# PIC32MK.net
KiCad netlist of a schematic drawn in Altium Designer
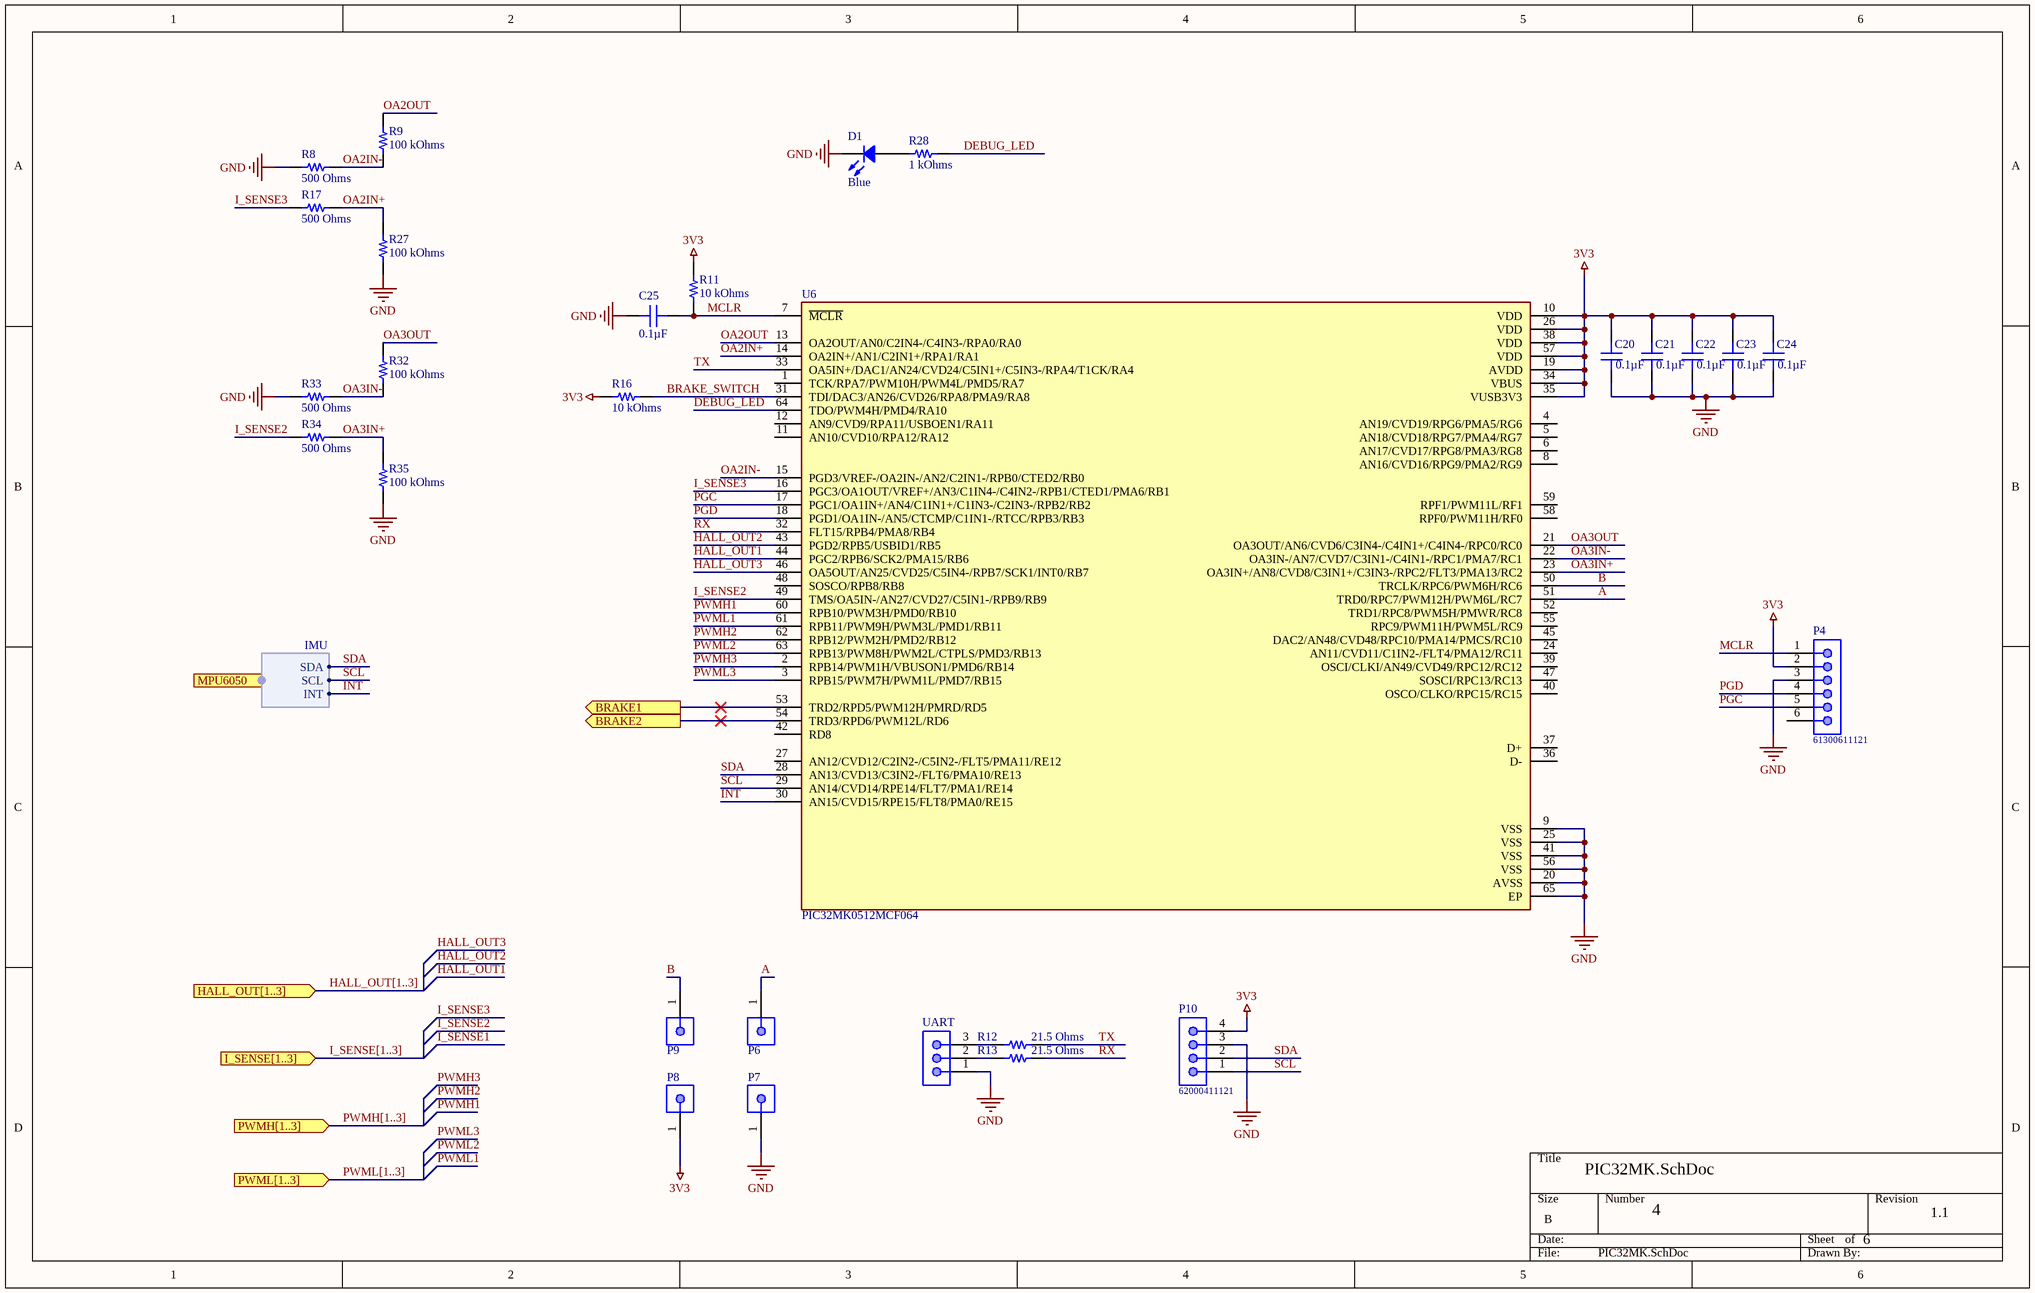
[diagram p0: PIC32MK.SchDoc]

(export (version "E")
  (design (tool "Eeschema 10.0.6"))
  (components
    (comp (ref "C20")
      (value "0.1µF")
      (footprint "CAP 0603_1608")
      (description "CAP CER 0.1UF 100V 0603 EPOXY")
      (fields
        (field (name "PART NUMBER") "GCG188R92A104KA03D")
        (field (name "MANUFACTURER") "Murata Electronics")
      )
      (libsource (lib "Celestial Altium Library - altium_library") (part "Capacitor"))
    )
    (comp (ref "C21")
      (value "0.1µF")
      (footprint "CAP 0603_1608")
      (description "CAP CER 0.1UF 100V 0603 EPOXY")
      (fields
        (field (name "PART NUMBER") "GCG188R92A104KA03D")
        (field (name "MANUFACTURER") "Murata Electronics")
      )
      (libsource (lib "Celestial Altium Library - altium_library") (part "Capacitor"))
    )
    (comp (ref "C22")
      (value "0.1µF")
      (footprint "CAP 0603_1608")
      (description "CAP CER 0.1UF 100V 0603 EPOXY")
      (fields
        (field (name "PART NUMBER") "GCG188R92A104KA03D")
        (field (name "MANUFACTURER") "Murata Electronics")
      )
      (libsource (lib "Celestial Altium Library - altium_library") (part "Capacitor"))
    )
    (comp (ref "C23")
      (value "0.1µF")
      (footprint "CAP 0603_1608")
      (description "CAP CER 0.1UF 100V 0603 EPOXY")
      (fields
        (field (name "PART NUMBER") "GCG188R92A104KA03D")
        (field (name "MANUFACTURER") "Murata Electronics")
      )
      (libsource (lib "Celestial Altium Library - altium_library") (part "Capacitor"))
    )
    (comp (ref "C24")
      (value "0.1µF")
      (footprint "CAP 0603_1608")
      (description "CAP CER 0.1UF 100V 0603 EPOXY")
      (fields
        (field (name "PART NUMBER") "GCG188R92A104KA03D")
        (field (name "MANUFACTURER") "Murata Electronics")
      )
      (libsource (lib "Celestial Altium Library - altium_library") (part "Capacitor"))
    )
    (comp (ref "C25")
      (value "0.1µF")
      (footprint "CAP 0603_1608")
      (description "CAP CER 0.1UF 100V 0603 EPOXY")
      (fields
        (field (name "PART NUMBER") "GCG188R92A104KA03D")
        (field (name "MANUFACTURER") "Murata Electronics")
      )
      (libsource (lib "Celestial Altium Library - altium_library") (part "Capacitor"))
    )
    (comp (ref "D1")
      (value "Blue")
      (footprint "LED 0603_1608 GREEN")
      (description "Blue LED")
      (fields (field (name "PART NUMBER") "XZCDGK53W-8VF") (field (name "MANUFACTURER") "SunLED"))
      (libsource (lib "Celestial Altium Library - altium_library") (part "LED"))
    )
    (comp (ref "P4")
      (value "61300611121")
      (footprint "61300611121")
      (description "WR-PHD Pin Header, THT, pitch 2.54mm, Single Row, Vertical, 6p")
      (fields (field (name "MANUFACTURER") "Wurth Elektronik"))
      (libsource (lib "Altium_WR-PHD") (part "61300611121"))
    )
    (comp (ref "P6")
      (value "61300111121")
      (footprint "61300111121")
      (description "WR-PHD Pin Header, THT, pitch 2.54mm, Single Row, Vertical, 1p")
      (fields (field (name "MANUFACTURER") "Wurth Elektronik"))
      (libsource (lib "Altium_WR-PHD") (part "61300111121"))
    )
    (comp (ref "P7")
      (value "61300111121")
      (footprint "61300111121")
      (description "WR-PHD Pin Header, THT, pitch 2.54mm, Single Row, Vertical, 1p")
      (fields (field (name "MANUFACTURER") "Wurth Elektronik"))
      (libsource (lib "Altium_WR-PHD") (part "61300111121"))
    )
    (comp (ref "P8")
      (value "61300111121")
      (footprint "61300111121")
      (description "WR-PHD Pin Header, THT, pitch 2.54mm, Single Row, Vertical, 1p")
      (fields (field (name "MANUFACTURER") "Wurth Elektronik"))
      (libsource (lib "Altium_WR-PHD") (part "61300111121"))
    )
    (comp (ref "P9")
      (value "61300111121")
      (footprint "61300111121")
      (description "WR-PHD Pin Header, THT, pitch 2.54mm, Single Row, Vertical, 1p")
      (fields (field (name "MANUFACTURER") "Wurth Elektronik"))
      (libsource (lib "Altium_WR-PHD") (part "61300111121"))
    )
    (comp (ref "P10")
      (value "62000411121")
      (footprint "62000411121")
      (description "WR-PHD Pin Header, THT, pitch 2mm, Single Row, Vertical, 4p")
      (fields (field (name "MANUFACTURER") "Wurth Elektronik"))
      (libsource (lib "Altium_WR-PHD") (part "62000411121"))
    )
    (comp (ref "R8")
      (value "500 Ohms")
      (footprint "RES 0603_1608")
      (description "RES SMD 500 OHM 0.05% 1/10W 0603")
      (fields (field (name "PART NUMBER") "TNPU0603500RAZEN00") (field (name "MANUFACTURER") "Vishay Dale"))
      (libsource (lib "Celestial Altium Library - altium_library") (part "Resistor"))
    )
    (comp (ref "R9")
      (value "100 kOhms")
      (footprint "RES 0603_1608")
      (description "RES SMD 100K OHM 1% 1/4W 0603")
      (fields (field (name "PART NUMBER") "RCA0603100KFKEAHP") (field (name "MANUFACTURER") "Vishay Dale"))
      (libsource (lib "Celestial Altium Library - altium_library") (part "Resistor"))
    )
    (comp (ref "R11")
      (value "10 kOhms")
      (footprint "RES 0603_1608")
      (description "RES 10K OHM 0.1% 1/16W 0603")
      (fields
        (field (name "PART NUMBER") "RNCS0603BKE10K0")
        (field (name "MANUFACTURER") "Stackpole Electronics Inc")
      )
      (libsource (lib "Celestial Altium Library - altium_library") (part "Resistor"))
    )
    (comp (ref "R12")
      (value "21.5 Ohms")
      (footprint "RES 0603_1608")
      (description "RES SMD 21.5 OHM 1% 1/10W 0603")
      (fields
        (field (name "PART NUMBER") "ERJ-3EKF21R5V")
        (field (name "MANUFACTURER") "Panasonic Electronic Components")
      )
      (libsource (lib "Celestial Altium Library - altium_library") (part "Resistor"))
    )
    (comp (ref "R13")
      (value "21.5 Ohms")
      (footprint "RES 0603_1608")
      (description "RES SMD 21.5 OHM 1% 1/10W 0603")
      (fields
        (field (name "PART NUMBER") "ERJ-3EKF21R5V")
        (field (name "MANUFACTURER") "Panasonic Electronic Components")
      )
      (libsource (lib "Celestial Altium Library - altium_library") (part "Resistor"))
    )
    (comp (ref "R16")
      (value "10 kOhms")
      (footprint "RES 0603_1608")
      (description "RES 10K OHM 0.1% 1/16W 0603")
      (fields
        (field (name "PART NUMBER") "RNCS0603BKE10K0")
        (field (name "MANUFACTURER") "Stackpole Electronics Inc")
      )
      (libsource (lib "Celestial Altium Library - altium_library") (part "Resistor"))
    )
    (comp (ref "R17")
      (value "500 Ohms")
      (footprint "RES 0603_1608")
      (description "RES SMD 500 OHM 0.05% 1/10W 0603")
      (fields (field (name "PART NUMBER") "TNPU0603500RAZEN00") (field (name "MANUFACTURER") "Vishay Dale"))
      (libsource (lib "Celestial Altium Library - altium_library") (part "Resistor"))
    )
    (comp (ref "R27")
      (value "100 kOhms")
      (footprint "RES 0603_1608")
      (description "RES SMD 100K OHM 1% 1/4W 0603")
      (fields (field (name "PART NUMBER") "RCA0603100KFKEAHP") (field (name "MANUFACTURER") "Vishay Dale"))
      (libsource (lib "Celestial Altium Library - altium_library") (part "Resistor"))
    )
    (comp (ref "R28")
      (value "1 kOhms")
      (footprint "RES 0603_1608")
      (description "RES 1K OHM 0.5% 1/10W 0603")
      (fields
        (field (name "PART NUMBER") "RNCF0603DTE1K00")
        (field (name "MANUFACTURER") "Stackpole Electronics Inc")
      )
      (libsource (lib "Celestial Altium Library - altium_library") (part "Resistor"))
    )
    (comp (ref "R32")
      (value "100 kOhms")
      (footprint "RES 0603_1608")
      (description "RES SMD 100K OHM 1% 1/4W 0603")
      (fields (field (name "PART NUMBER") "RCA0603100KFKEAHP") (field (name "MANUFACTURER") "Vishay Dale"))
      (libsource (lib "Celestial Altium Library - altium_library") (part "Resistor"))
    )
    (comp (ref "R33")
      (value "500 Ohms")
      (footprint "RES 0603_1608")
      (description "RES SMD 500 OHM 0.05% 1/10W 0603")
      (fields (field (name "PART NUMBER") "TNPU0603500RAZEN00") (field (name "MANUFACTURER") "Vishay Dale"))
      (libsource (lib "Celestial Altium Library - altium_library") (part "Resistor"))
    )
    (comp (ref "R34")
      (value "500 Ohms")
      (footprint "RES 0603_1608")
      (description "RES SMD 500 OHM 0.05% 1/10W 0603")
      (fields (field (name "PART NUMBER") "TNPU0603500RAZEN00") (field (name "MANUFACTURER") "Vishay Dale"))
      (libsource (lib "Celestial Altium Library - altium_library") (part "Resistor"))
    )
    (comp (ref "R35")
      (value "100 kOhms")
      (footprint "RES 0603_1608")
      (description "RES SMD 100K OHM 1% 1/4W 0603")
      (fields (field (name "PART NUMBER") "RCA0603100KFKEAHP") (field (name "MANUFACTURER") "Vishay Dale"))
      (libsource (lib "Celestial Altium Library - altium_library") (part "Resistor"))
    )
    (comp (ref "U6")
      (value "PIC32MK0512MCF064")
      (footprint "QFN50P900X900X100-65N")
      (description "PIC32MK Microcontroller IC 32-Bit 120MHz 1MB _1M x 8_ FLASH 64-TQFP _10x10_")
      (fields
        (field (name "MP") "PIC32MK1024MCF064-I/PT")
        (field (name "DIGI-KEY_PART_NUMBER") "PIC32MK1024MCF064-I/PT-ND")
      )
      (libsource (lib "IC") (part "PIC32MK0512MCF064"))
    )
    (comp (ref "UART")
      (value "3 pin 2mm JST Male")
      (footprint "3pin - 2mm header")
      (libsource (lib "IC") (part "3 pin 2mm JST Male"))
    )
  )
  (nets
    (net (code "2") (name "/A") (class "Default")
      (node (ref "P6") (pin "1") (pinfunction "1_1") (pintype "passive"))
      (node (ref "U6") (pin "51") (pinfunction "TRD0/RPC7/PWM12H/PWM6L/RC7_51") (pintype "passive"))
    )
    (net (code "3") (name "/B") (class "Default")
      (node (ref "P9") (pin "1") (pinfunction "1_1") (pintype "passive"))
      (node (ref "U6") (pin "50") (pinfunction "TRCLK/RPC6/PWM6H/RC6_50") (pintype "passive"))
    )
    (net (code "4") (name "/BRAKE1") (class "Default")
      (node (ref "U6") (pin "53") (pinfunction "TRD2/RPD5/PWM12H/PMRD/RD5_53") (pintype "passive"))
    )
    (net (code "5") (name "/BRAKE2") (class "Default")
      (node (ref "U6") (pin "54") (pinfunction "TRD3/RPD6/PWM12L/RD6_54") (pintype "passive"))
    )
    (net (code "6") (name "/BRAKE_SWITCH") (class "Default")
      (node (ref "R16") (pin "1") (pinfunction "1_1") (pintype "passive"))
      (node (ref "U6") (pin "31") (pinfunction "TDI/DAC3/AN26/CVD26/RPA8/PMA9/RA8_31") (pintype "passive"))
    )
    (net (code "7") (name "/DEBUG_LED") (class "Default")
      (node (ref "R28") (pin "1") (pinfunction "1_1") (pintype "passive"))
      (node (ref "U6") (pin "64") (pinfunction "TDO/PWM4H/PMD4/RA10_64") (pintype "passive"))
    )
    (net (code "8") (name "/HALL_OUT1") (class "Default")
      (node (ref "U6") (pin "44") (pinfunction "PGC2/RPB6/SCK2/PMA15/RB6_44") (pintype "passive"))
    )
    (net (code "9") (name "/HALL_OUT2") (class "Default")
      (node (ref "U6") (pin "43") (pinfunction "PGD2/RPB5/USBID1/RB5_43") (pintype "passive"))
    )
    (net (code "10") (name "/HALL_OUT3") (class "Default")
      (node (ref "U6") (pin "46") (pinfunction "OA5OUT/AN25/CVD25/C5IN4-/RPB7/SCK1/INT0/RB7_46") (pintype "passive"))
    )
    (net (code "12") (name "/INT") (class "Default")
      (node (ref "U6") (pin "30") (pinfunction "AN15/CVD15/RPE15/FLT8/PMA0/RE15_30") (pintype "passive"))
    )
    (net (code "14") (name "/I_SENSE2") (class "Default")
      (node (ref "R34") (pin "1") (pinfunction "1_1") (pintype "passive"))
      (node (ref "U6") (pin "49") (pinfunction "TMS/OA5IN-/AN27/CVD27/C5IN1-/RPB9/RB9_49") (pintype "passive"))
    )
    (net (code "15") (name "/I_SENSE3") (class "Default")
      (node (ref "R17") (pin "1") (pinfunction "1_1") (pintype "passive"))
      (node (ref "U6") (pin "16") (pinfunction "PGC3/OA1OUT/VREF+/AN3/C1IN4-/C4IN2-/RPB1/CTED1/PMA6/RB1_16") (pintype "passive"))
    )
    (net (code "17") (name "/MCLR") (class "Default")
      (node (ref "C25") (pin "1") (pinfunction "1_1") (pintype "passive"))
      (node (ref "P4") (pin "1") (pinfunction "1_1") (pintype "passive"))
      (node (ref "R11") (pin "1") (pinfunction "1_1") (pintype "passive"))
      (node (ref "U6") (pin "7") (pinfunction "~{MCLR}_7") (pintype "passive"))
    )
    (net (code "18") (name "/OA2IN+") (class "Default")
      (node (ref "R17") (pin "2") (pinfunction "2_2") (pintype "passive"))
      (node (ref "R27") (pin "2") (pinfunction "2_2") (pintype "passive"))
      (node (ref "U6") (pin "14") (pinfunction "OA2IN+/AN1/C2IN1+/RPA1/RA1_14") (pintype "passive"))
    )
    (net (code "19") (name "/OA2IN-") (class "Default")
      (node (ref "R8") (pin "2") (pinfunction "2_2") (pintype "passive"))
      (node (ref "R9") (pin "1") (pinfunction "1_1") (pintype "passive"))
      (node (ref "U6") (pin "15") (pinfunction "PGD3/VREF-/OA2IN-/AN2/C2IN1-/RPB0/CTED2/RB0_15") (pintype "passive"))
    )
    (net (code "20") (name "/OA2OUT") (class "Default")
      (node (ref "R9") (pin "2") (pinfunction "2_2") (pintype "passive"))
      (node (ref "U6") (pin "13") (pinfunction "OA2OUT/AN0/C2IN4-/C4IN3-/RPA0/RA0_13") (pintype "passive"))
    )
    (net (code "21") (name "/OA3IN+") (class "Default")
      (node (ref "R34") (pin "2") (pinfunction "2_2") (pintype "passive"))
      (node (ref "R35") (pin "2") (pinfunction "2_2") (pintype "passive"))
      (node (ref "U6") (pin "23") (pinfunction "OA3IN+/AN8/CVD8/C3IN1+/C3IN3-/RPC2/FLT3/PMA13/RC2_23") (pintype "passive"))
    )
    (net (code "22") (name "/OA3IN-") (class "Default")
      (node (ref "R32") (pin "1") (pinfunction "1_1") (pintype "passive"))
      (node (ref "R33") (pin "2") (pinfunction "2_2") (pintype "passive"))
      (node (ref "U6") (pin "22") (pinfunction "OA3IN-/AN7/CVD7/C3IN1-/C4IN1-/RPC1/PMA7/RC1_22") (pintype "passive"))
    )
    (net (code "23") (name "/OA3OUT") (class "Default")
      (node (ref "R32") (pin "2") (pinfunction "2_2") (pintype "passive"))
      (node (ref "U6") (pin "21") (pinfunction "OA3OUT/AN6/CVD6/C3IN4-/C4IN1+/C4IN4-/RPC0/RC0_21") (pintype "passive"))
    )
    (net (code "24") (name "/PGC") (class "Default")
      (node (ref "P4") (pin "5") (pinfunction "5_5") (pintype "passive"))
      (node (ref "U6") (pin "17") (pinfunction "PGC1/OA1IN+/AN4/C1IN1+/C1IN3-/C2IN3-/RPB2/RB2_17") (pintype "passive"))
    )
    (net (code "25") (name "/PGD") (class "Default")
      (node (ref "P4") (pin "4") (pinfunction "4_4") (pintype "passive"))
      (node (ref "U6") (pin "18") (pinfunction "PGD1/OA1IN-/AN5/CTCMP/C1IN1-/RTCC/RPB3/RB3_18") (pintype "passive"))
    )
    (net (code "26") (name "/PWMH1") (class "Default")
      (node (ref "U6") (pin "60") (pinfunction "RPB10/PWM3H/PMD0/RB10_60") (pintype "passive"))
    )
    (net (code "27") (name "/PWMH2") (class "Default")
      (node (ref "U6") (pin "62") (pinfunction "RPB12/PWM2H/PMD2/RB12_62") (pintype "passive"))
    )
    (net (code "28") (name "/PWMH3") (class "Default")
      (node (ref "U6") (pin "2") (pinfunction "RPB14/PWM1H/VBUSON1/PMD6/RB14_2") (pintype "passive"))
    )
    (net (code "30") (name "/PWML1") (class "Default")
      (node (ref "U6") (pin "61") (pinfunction "RPB11/PWM9H/PWM3L/PMD1/RB11_61") (pintype "passive"))
    )
    (net (code "31") (name "/PWML2") (class "Default")
      (node (ref "U6") (pin "63") (pinfunction "RPB13/PWM8H/PWM2L/CTPLS/PMD3/RB13_63") (pintype "passive"))
    )
    (net (code "32") (name "/PWML3") (class "Default")
      (node (ref "U6") (pin "3") (pinfunction "RPB15/PWM7H/PWM1L/PMD7/RB15_3") (pintype "passive"))
    )
    (net (code "34") (name "/RX") (class "Default")
      (node (ref "R13") (pin "2") (pinfunction "2_2") (pintype "passive"))
      (node (ref "U6") (pin "32") (pinfunction "FLT15/RPB4/PMA8/RB4_32") (pintype "passive"))
    )
    (net (code "35") (name "/SCL") (class "Default")
      (node (ref "P10") (pin "1") (pinfunction "1_1") (pintype "passive"))
      (node (ref "U6") (pin "29") (pinfunction "AN14/CVD14/RPE14/FLT7/PMA1/RE14_29") (pintype "passive"))
    )
    (net (code "36") (name "/SDA") (class "Default")
      (node (ref "P10") (pin "2") (pinfunction "2_2") (pintype "passive"))
      (node (ref "U6") (pin "28") (pinfunction "AN13/CVD13/C3IN2-/FLT6/PMA10/RE13_28") (pintype "passive"))
    )
    (net (code "37") (name "/TX") (class "Default")
      (node (ref "R12") (pin "2") (pinfunction "2_2") (pintype "passive"))
      (node (ref "U6") (pin "33") (pinfunction "OA5IN+/DAC1/AN24/CVD24/C5IN1+/C5IN3-/RPA4/T1CK/RA4_33") (pintype "passive"))
    )
    (net (code "39") (name "3V3") (class "Default")
      (node (ref "C20") (pin "1") (pinfunction "1_1") (pintype "passive"))
      (node (ref "C21") (pin "1") (pinfunction "1_1") (pintype "passive"))
      (node (ref "C22") (pin "1") (pinfunction "1_1") (pintype "passive"))
      (node (ref "C23") (pin "1") (pinfunction "1_1") (pintype "passive"))
      (node (ref "C24") (pin "1") (pinfunction "1_1") (pintype "passive"))
      (node (ref "P10") (pin "4") (pinfunction "4_4") (pintype "passive"))
      (node (ref "P4") (pin "2") (pinfunction "2_2") (pintype "passive"))
      (node (ref "P8") (pin "1") (pinfunction "1_1") (pintype "passive"))
      (node (ref "R11") (pin "2") (pinfunction "2_2") (pintype "passive"))
      (node (ref "R16") (pin "2") (pinfunction "2_2") (pintype "passive"))
      (node (ref "U6") (pin "10") (pinfunction "VDD_10") (pintype "power_in"))
      (node (ref "U6") (pin "19") (pinfunction "AVDD_19") (pintype "power_in"))
      (node (ref "U6") (pin "26") (pinfunction "VDD_26") (pintype "power_in"))
      (node (ref "U6") (pin "34") (pinfunction "VBUS_34") (pintype "power_in"))
      (node (ref "U6") (pin "35") (pinfunction "VUSB3V3_35") (pintype "passive"))
      (node (ref "U6") (pin "38") (pinfunction "VDD_38") (pintype "power_in"))
      (node (ref "U6") (pin "57") (pinfunction "VDD_57") (pintype "power_in"))
    )
    (net (code "40") (name "GND") (class "Default")
      (node (ref "C20") (pin "2") (pinfunction "2_2") (pintype "passive"))
      (node (ref "C21") (pin "2") (pinfunction "2_2") (pintype "passive"))
      (node (ref "C22") (pin "2") (pinfunction "2_2") (pintype "passive"))
      (node (ref "C23") (pin "2") (pinfunction "2_2") (pintype "passive"))
      (node (ref "C24") (pin "2") (pinfunction "2_2") (pintype "passive"))
      (node (ref "C25") (pin "2") (pinfunction "2_2") (pintype "passive"))
      (node (ref "D1") (pin "2") (pinfunction "2_2") (pintype "passive"))
      (node (ref "P10") (pin "3") (pinfunction "3_3") (pintype "passive"))
      (node (ref "P4") (pin "3") (pinfunction "3_3") (pintype "passive"))
      (node (ref "P7") (pin "1") (pinfunction "1_1") (pintype "passive"))
      (node (ref "R27") (pin "1") (pinfunction "1_1") (pintype "passive"))
      (node (ref "R33") (pin "1") (pinfunction "1_1") (pintype "passive"))
      (node (ref "R35") (pin "1") (pinfunction "1_1") (pintype "passive"))
      (node (ref "R8") (pin "1") (pinfunction "1_1") (pintype "passive"))
      (node (ref "U6") (pin "20") (pinfunction "AVSS_20") (pintype "power_in"))
      (node (ref "U6") (pin "25") (pinfunction "VSS_25") (pintype "power_in"))
      (node (ref "U6") (pin "41") (pinfunction "VSS_41") (pintype "power_in"))
      (node (ref "U6") (pin "56") (pinfunction "VSS_56") (pintype "power_in"))
      (node (ref "U6") (pin "65") (pinfunction "EP_65") (pintype "power_in"))
      (node (ref "U6") (pin "9") (pinfunction "VSS_9") (pintype "power_in"))
      (node (ref "UART") (pin "1") (pinfunction "1_1") (pintype "passive"))
    )
    (net (code "41") (name "Net-(D1-Pad1)") (class "Default")
      (node (ref "D1") (pin "1") (pinfunction "1_1") (pintype "passive"))
      (node (ref "R28") (pin "2") (pinfunction "2_2") (pintype "passive"))
    )
    (net (code "42") (name "Net-(R12-Pad1)") (class "Default")
      (node (ref "R12") (pin "1") (pinfunction "1_1") (pintype "passive"))
      (node (ref "UART") (pin "3") (pinfunction "3_3") (pintype "passive"))
    )
    (net (code "43") (name "Net-(R13-Pad1)") (class "Default")
      (node (ref "R13") (pin "1") (pinfunction "1_1") (pintype "passive"))
      (node (ref "UART") (pin "2") (pinfunction "2_2") (pintype "passive"))
    )
    (net (code "44") (name "unconnected-(P4-Pad6)") (class "Default")
      (node (ref "P4") (pin "6") (pinfunction "6_6") (pintype "passive"))
    )
    (net (code "45") (name "unconnected-(U6-AN9{slash}CVD9{slash}RPA11{slash}USBOEN1{slash}RA11-Pad12)") (class "Default")
      (node (ref "U6") (pin "12") (pinfunction "AN9/CVD9/RPA11/USBOEN1/RA11_12") (pintype "passive"))
    )
    (net (code "46") (name "unconnected-(U6-AN10{slash}CVD10{slash}RPA12{slash}RA12-Pad11)") (class "Default")
      (node (ref "U6") (pin "11") (pinfunction "AN10/CVD10/RPA12/RA12_11") (pintype "passive"))
    )
    (net (code "47") (name "unconnected-(U6-AN11{slash}CVD11{slash}C1IN2-{slash}FLT4{slash}PMA12{slash}RC11-Pad24)") (class "Default")
      (node (ref "U6") (pin "24") (pinfunction "AN11/CVD11/C1IN2-/FLT4/PMA12/RC11_24") (pintype "passive"))
    )
    (net (code "48") (name "unconnected-(U6-AN12{slash}CVD12{slash}C2IN2-{slash}C5IN2-{slash}FLT5{slash}PMA11{slash}RE12-Pad27)") (class "Default")
      (node (ref "U6") (pin "27") (pinfunction "AN12/CVD12/C2IN2-/C5IN2-/FLT5/PMA11/RE12_27") (pintype "passive"))
    )
    (net (code "49") (name "unconnected-(U6-AN16{slash}CVD16{slash}RPG9{slash}PMA2{slash}RG9-Pad8)") (class "Default")
      (node (ref "U6") (pin "8") (pinfunction "AN16/CVD16/RPG9/PMA2/RG9_8") (pintype "passive"))
    )
    (net (code "50") (name "unconnected-(U6-AN17{slash}CVD17{slash}RPG8{slash}PMA3{slash}RG8-Pad6)") (class "Default")
      (node (ref "U6") (pin "6") (pinfunction "AN17/CVD17/RPG8/PMA3/RG8_6") (pintype "passive"))
    )
    (net (code "51") (name "unconnected-(U6-AN18{slash}CVD18{slash}RPG7{slash}PMA4{slash}RG7-Pad5)") (class "Default")
      (node (ref "U6") (pin "5") (pinfunction "AN18/CVD18/RPG7/PMA4/RG7_5") (pintype "passive"))
    )
    (net (code "52") (name "unconnected-(U6-AN19{slash}CVD19{slash}RPG6{slash}PMA5{slash}RG6-Pad4)") (class "Default")
      (node (ref "U6") (pin "4") (pinfunction "AN19/CVD19/RPG6/PMA5/RG6_4") (pintype "passive"))
    )
    (net (code "53") (name "unconnected-(U6-D+-Pad37)") (class "Default")
      (node (ref "U6") (pin "37") (pinfunction "D+_37") (pintype "passive"))
    )
    (net (code "54") (name "unconnected-(U6-D--Pad36)") (class "Default")
      (node (ref "U6") (pin "36") (pinfunction "D-_36") (pintype "passive"))
    )
    (net (code "55") (name "unconnected-(U6-DAC2{slash}AN48{slash}CVD48{slash}RPC10{slash}PMA14{slash}PMCS{slash}RC10-Pad45)") (class "Default")
      (node (ref "U6") (pin "45") (pinfunction "DAC2/AN48/CVD48/RPC10/PMA14/PMCS/RC10_45") (pintype "passive"))
    )
    (net (code "56") (name "unconnected-(U6-OSCI{slash}CLKI{slash}AN49{slash}CVD49{slash}RPC12{slash}RC12-Pad39)") (class "Default")
      (node (ref "U6") (pin "39") (pinfunction "OSCI/CLKI/AN49/CVD49/RPC12/RC12_39") (pintype "passive"))
    )
    (net (code "57") (name "unconnected-(U6-OSCO{slash}CLKO{slash}RPC15{slash}RC15-Pad40)") (class "Default")
      (node (ref "U6") (pin "40") (pinfunction "OSCO/CLKO/RPC15/RC15_40") (pintype "passive"))
    )
    (net (code "58") (name "unconnected-(U6-RD8-Pad42)") (class "Default")
      (node (ref "U6") (pin "42") (pinfunction "RD8_42") (pintype "passive"))
    )
    (net (code "59") (name "unconnected-(U6-RPC9{slash}PWM11H{slash}PWM5L{slash}RC9-Pad55)") (class "Default")
      (node (ref "U6") (pin "55") (pinfunction "RPC9/PWM11H/PWM5L/RC9_55") (pintype "passive"))
    )
    (net (code "60") (name "unconnected-(U6-RPF0{slash}PWM11H{slash}RF0-Pad58)") (class "Default")
      (node (ref "U6") (pin "58") (pinfunction "RPF0/PWM11H/RF0_58") (pintype "passive"))
    )
    (net (code "61") (name "unconnected-(U6-RPF1{slash}PWM11L{slash}RF1-Pad59)") (class "Default")
      (node (ref "U6") (pin "59") (pinfunction "RPF1/PWM11L/RF1_59") (pintype "passive"))
    )
    (net (code "62") (name "unconnected-(U6-SOSCI{slash}RPC13{slash}RC13-Pad47)") (class "Default")
      (node (ref "U6") (pin "47") (pinfunction "SOSCI/RPC13/RC13_47") (pintype "passive"))
    )
    (net (code "63") (name "unconnected-(U6-SOSCO{slash}RPB8{slash}RB8-Pad48)") (class "Default")
      (node (ref "U6") (pin "48") (pinfunction "SOSCO/RPB8/RB8_48") (pintype "passive"))
    )
    (net (code "64") (name "unconnected-(U6-TCK{slash}RPA7{slash}PWM10H{slash}PWM4L{slash}PMD5{slash}RA7-Pad1)") (class "Default")
      (node (ref "U6") (pin "1") (pinfunction "TCK/RPA7/PWM10H/PWM4L/PMD5/RA7_1") (pintype "passive"))
    )
    (net (code "65") (name "unconnected-(U6-TRD1{slash}RPC8{slash}PWM5H{slash}PMWR{slash}RC8-Pad52)") (class "Default")
      (node (ref "U6") (pin "52") (pinfunction "TRD1/RPC8/PWM5H/PMWR/RC8_52") (pintype "passive"))
    )
  )
)
